# sensorboard.net
KiCad netlist of a schematic drawn in EAGLE
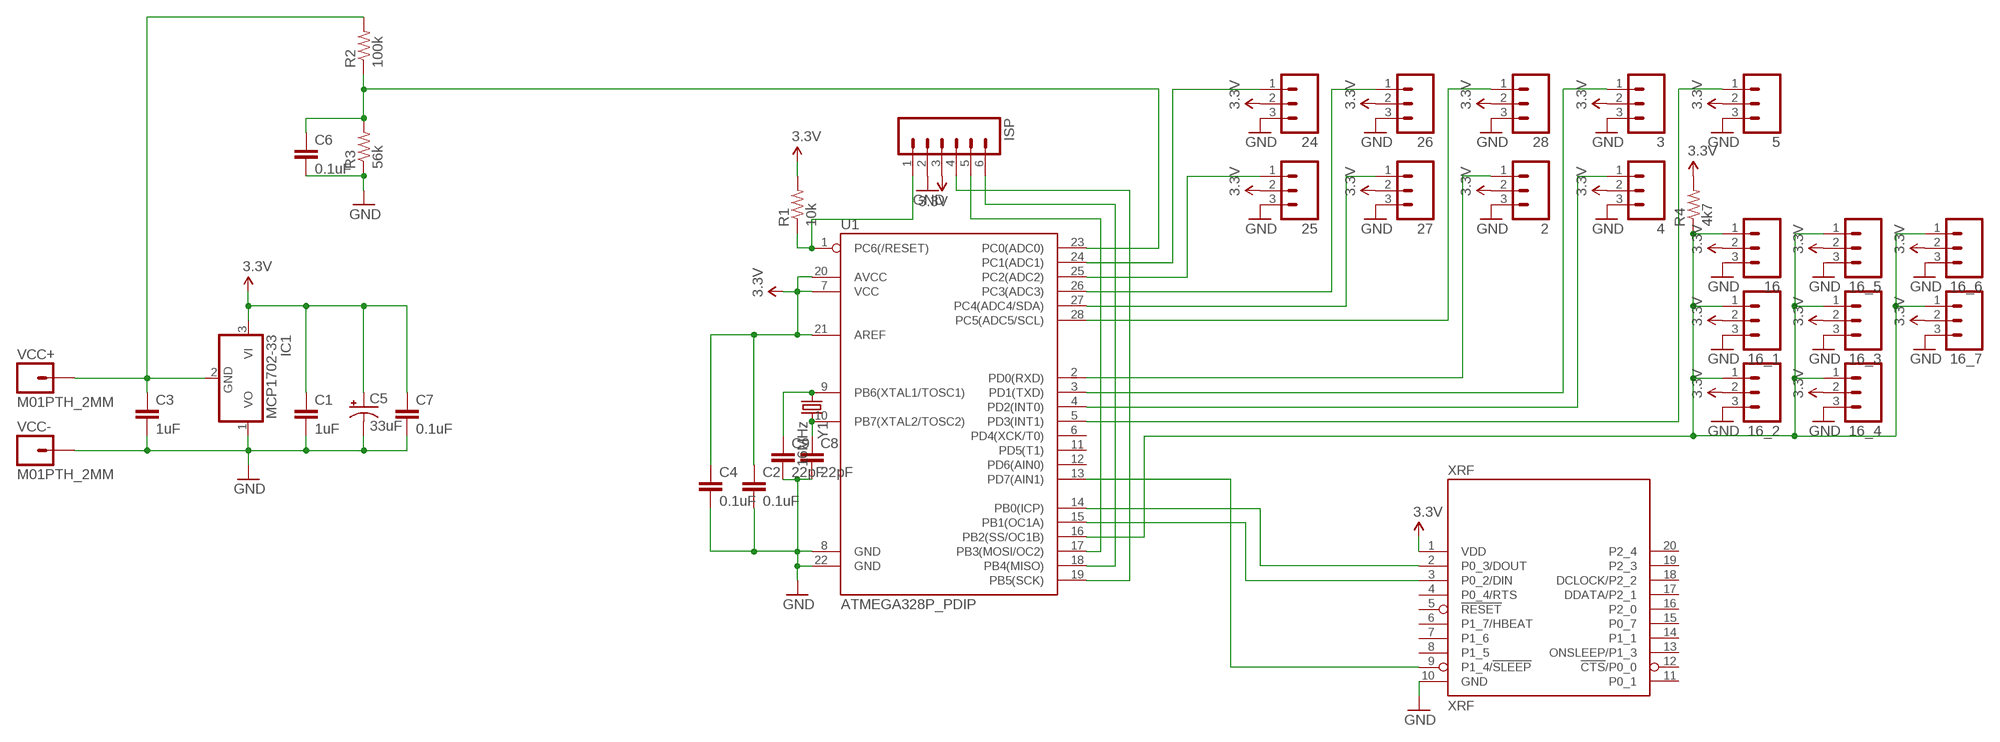
[diagram p0: schematic, sheet 1]

(export (version "E")
  (design (tool "Eeschema 10.0.6"))
  (components
    (comp (ref "2")
      (value "M031X03_NO_SILK")
      (footprint "eagle-import:1X03_NO_SILK")
      (libsource (lib "eagle-import") (part "M031X03_NO_SILK"))
    )
    (comp (ref "3")
      (value "M031X03_NO_SILK")
      (footprint "eagle-import:1X03_NO_SILK")
      (libsource (lib "eagle-import") (part "M031X03_NO_SILK"))
    )
    (comp (ref "4")
      (value "M031X03_NO_SILK")
      (footprint "eagle-import:1X03_NO_SILK")
      (libsource (lib "eagle-import") (part "M031X03_NO_SILK"))
    )
    (comp (ref "5")
      (value "M031X03_NO_SILK")
      (footprint "eagle-import:1X03_NO_SILK")
      (libsource (lib "eagle-import") (part "M031X03_NO_SILK"))
    )
    (comp (ref "16")
      (value "M031X03_NO_SILK")
      (footprint "eagle-import:1X03_NO_SILK")
      (libsource (lib "eagle-import") (part "M031X03_NO_SILK"))
    )
    (comp (ref "16_1")
      (value "M031X03_NO_SILK")
      (footprint "eagle-import:1X03_NO_SILK")
      (libsource (lib "eagle-import") (part "M031X03_NO_SILK"))
    )
    (comp (ref "16_2")
      (value "M031X03_NO_SILK")
      (footprint "eagle-import:1X03_NO_SILK")
      (libsource (lib "eagle-import") (part "M031X03_NO_SILK"))
    )
    (comp (ref "16_3")
      (value "M031X03_NO_SILK")
      (footprint "eagle-import:1X03_NO_SILK")
      (libsource (lib "eagle-import") (part "M031X03_NO_SILK"))
    )
    (comp (ref "16_4")
      (value "M031X03_NO_SILK")
      (footprint "eagle-import:1X03_NO_SILK")
      (libsource (lib "eagle-import") (part "M031X03_NO_SILK"))
    )
    (comp (ref "16_5")
      (value "M031X03_NO_SILK")
      (footprint "eagle-import:1X03_NO_SILK")
      (libsource (lib "eagle-import") (part "M031X03_NO_SILK"))
    )
    (comp (ref "16_6")
      (value "M031X03_NO_SILK")
      (footprint "eagle-import:1X03_NO_SILK")
      (libsource (lib "eagle-import") (part "M031X03_NO_SILK"))
    )
    (comp (ref "16_7")
      (value "M031X03_NO_SILK")
      (footprint "eagle-import:1X03_NO_SILK")
      (libsource (lib "eagle-import") (part "M031X03_NO_SILK"))
    )
    (comp (ref "24")
      (value "M031X03_NO_SILK")
      (footprint "eagle-import:1X03_NO_SILK")
      (libsource (lib "eagle-import") (part "M031X03_NO_SILK"))
    )
    (comp (ref "25")
      (value "M031X03_NO_SILK")
      (footprint "eagle-import:1X03_NO_SILK")
      (libsource (lib "eagle-import") (part "M031X03_NO_SILK"))
    )
    (comp (ref "26")
      (value "M031X03_NO_SILK")
      (footprint "eagle-import:1X03_NO_SILK")
      (libsource (lib "eagle-import") (part "M031X03_NO_SILK"))
    )
    (comp (ref "27")
      (value "M031X03_NO_SILK")
      (footprint "eagle-import:1X03_NO_SILK")
      (libsource (lib "eagle-import") (part "M031X03_NO_SILK"))
    )
    (comp (ref "28")
      (value "M031X03_NO_SILK")
      (footprint "eagle-import:1X03_NO_SILK")
      (libsource (lib "eagle-import") (part "M031X03_NO_SILK"))
    )
    (comp (ref "C1")
      (value "1uF")
      (footprint "eagle-import:CAP-PTH-SMALLEZ")
      (libsource (lib "eagle-import") (part "CAPEZ"))
    )
    (comp (ref "C2")
      (value "0.1uF")
      (footprint "eagle-import:CAP-PTH-SMALLEZ")
      (libsource (lib "eagle-import") (part "CAPEZ"))
    )
    (comp (ref "C3")
      (value "1uF")
      (footprint "eagle-import:CAP-PTH-SMALLEZ")
      (libsource (lib "eagle-import") (part "CAPEZ"))
    )
    (comp (ref "C4")
      (value "0.1uF")
      (footprint "eagle-import:CAP-PTH-SMALLEZ")
      (libsource (lib "eagle-import") (part "CAPEZ"))
    )
    (comp (ref "C5")
      (value "33uF")
      (footprint "eagle-import:CPOL-RADIAL-10UF-25V")
      (libsource (lib "eagle-import") (part "CAP_POLPTH2"))
    )
    (comp (ref "C6")
      (value "0.1uF")
      (footprint "eagle-import:CAP-PTH-SMALLEZ")
      (libsource (lib "eagle-import") (part "CAPEZ"))
    )
    (comp (ref "C7")
      (value "0.1uF")
      (footprint "eagle-import:CAP-PTH-SMALLEZ")
      (libsource (lib "eagle-import") (part "CAPEZ"))
    )
    (comp (ref "C8")
      (value "22pF")
      (footprint "eagle-import:CAP-PTH-SMALLEZ")
      (libsource (lib "eagle-import") (part "CAPEZ"))
    )
    (comp (ref "C9")
      (value "22pF")
      (footprint "eagle-import:CAP-PTH-SMALLEZ")
      (libsource (lib "eagle-import") (part "CAPEZ"))
    )
    (comp (ref "IC1")
      (value "MCP1702-33")
      (footprint "eagle-import:TO92")
      (libsource (lib "eagle-import") (part "78ZL05"))
    )
    (comp (ref "ISP")
      (value "M06SIP")
      (footprint "eagle-import:1X06")
      (libsource (lib "eagle-import") (part "M06SIP"))
    )
    (comp (ref "R1")
      (value "10k")
      (footprint "eagle-import:AXIAL-0.3EZ")
      (libsource (lib "eagle-import") (part "RESISTOREZ"))
    )
    (comp (ref "R2")
      (value "100k")
      (footprint "eagle-import:AXIAL-0.3EZ")
      (libsource (lib "eagle-import") (part "RESISTOREZ"))
    )
    (comp (ref "R3")
      (value "56k")
      (footprint "eagle-import:AXIAL-0.3EZ")
      (libsource (lib "eagle-import") (part "RESISTOREZ"))
    )
    (comp (ref "R4")
      (value "4k7")
      (footprint "eagle-import:AXIAL-0.3EZ")
      (libsource (lib "eagle-import") (part "RESISTOREZ"))
    )
    (comp (ref "U1")
      (value "ATMEGA328P_PDIP")
      (footprint "eagle-import:DIL28-3")
      (libsource (lib "eagle-import") (part "ATMEGA328P_PDIP"))
    )
    (comp (ref "VCC+")
      (value "M01PTH_2MM")
      (footprint "eagle-import:1X01_2MM")
      (libsource (lib "eagle-import") (part "M01PTH_2MM"))
    )
    (comp (ref "VCC-")
      (value "M01PTH_2MM")
      (footprint "eagle-import:1X01_2MM")
      (libsource (lib "eagle-import") (part "M01PTH_2MM"))
    )
    (comp (ref "XRF")
      (value "XRF")
      (footprint "eagle-import:XRF")
      (libsource (lib "eagle-import") (part "XRFXRF"))
    )
    (comp (ref "Y1")
      (value "16MHz")
      (footprint "eagle-import:HC49US")
      (libsource (lib "eagle-import") (part "CRYSTALHC49US"))
    )
  )
  (nets
    (net (code "1") (name "3.3V") (class "Default")
      (node (ref "16") (pin "2") (pinfunction "2_2") (pintype "passive"))
      (node (ref "16_1") (pin "2") (pinfunction "2_2") (pintype "passive"))
      (node (ref "16_2") (pin "2") (pinfunction "2_2") (pintype "passive"))
      (node (ref "16_3") (pin "2") (pinfunction "2_2") (pintype "passive"))
      (node (ref "16_4") (pin "2") (pinfunction "2_2") (pintype "passive"))
      (node (ref "16_5") (pin "2") (pinfunction "2_2") (pintype "passive"))
      (node (ref "16_6") (pin "2") (pinfunction "2_2") (pintype "passive"))
      (node (ref "16_7") (pin "2") (pinfunction "2_2") (pintype "passive"))
      (node (ref "2") (pin "2") (pinfunction "2_2") (pintype "passive"))
      (node (ref "24") (pin "2") (pinfunction "2_2") (pintype "passive"))
      (node (ref "25") (pin "2") (pinfunction "2_2") (pintype "passive"))
      (node (ref "26") (pin "2") (pinfunction "2_2") (pintype "passive"))
      (node (ref "27") (pin "2") (pinfunction "2_2") (pintype "passive"))
      (node (ref "28") (pin "2") (pinfunction "2_2") (pintype "passive"))
      (node (ref "3") (pin "2") (pinfunction "2_2") (pintype "passive"))
      (node (ref "4") (pin "2") (pinfunction "2_2") (pintype "passive"))
      (node (ref "5") (pin "2") (pinfunction "2_2") (pintype "passive"))
      (node (ref "C1") (pin "1") (pinfunction "1_1") (pintype "passive"))
      (node (ref "C2") (pin "1") (pinfunction "1_1") (pintype "passive"))
      (node (ref "C4") (pin "1") (pinfunction "1_1") (pintype "passive"))
      (node (ref "C5") (pin "1") (pinfunction "+_1") (pintype "passive"))
      (node (ref "C7") (pin "1") (pinfunction "1_1") (pintype "passive"))
      (node (ref "IC1") (pin "3") (pinfunction "VI_3") (pintype "input"))
      (node (ref "ISP") (pin "3") (pinfunction "3_3") (pintype "passive"))
      (node (ref "R1") (pin "P$2") (pinfunction "2_P$2") (pintype "passive"))
      (node (ref "R4") (pin "P$2") (pinfunction "2_P$2") (pintype "passive"))
      (node (ref "U1") (pin "20") (pinfunction "AVCC_20") (pintype "bidirectional"))
      (node (ref "U1") (pin "21") (pinfunction "AREF_21") (pintype "bidirectional"))
      (node (ref "U1") (pin "7") (pinfunction "VCC_7") (pintype "bidirectional"))
      (node (ref "XRF") (pin "1") (pinfunction "VDD_1") (pintype "power_in"))
    )
    (net (code "2") (name "GND") (class "Default")
      (node (ref "16") (pin "3") (pinfunction "3_3") (pintype "passive"))
      (node (ref "16_1") (pin "3") (pinfunction "3_3") (pintype "passive"))
      (node (ref "16_2") (pin "3") (pinfunction "3_3") (pintype "passive"))
      (node (ref "16_3") (pin "3") (pinfunction "3_3") (pintype "passive"))
      (node (ref "16_4") (pin "3") (pinfunction "3_3") (pintype "passive"))
      (node (ref "16_5") (pin "3") (pinfunction "3_3") (pintype "passive"))
      (node (ref "16_6") (pin "3") (pinfunction "3_3") (pintype "passive"))
      (node (ref "16_7") (pin "3") (pinfunction "3_3") (pintype "passive"))
      (node (ref "2") (pin "3") (pinfunction "3_3") (pintype "passive"))
      (node (ref "24") (pin "3") (pinfunction "3_3") (pintype "passive"))
      (node (ref "25") (pin "3") (pinfunction "3_3") (pintype "passive"))
      (node (ref "26") (pin "3") (pinfunction "3_3") (pintype "passive"))
      (node (ref "27") (pin "3") (pinfunction "3_3") (pintype "passive"))
      (node (ref "28") (pin "3") (pinfunction "3_3") (pintype "passive"))
      (node (ref "3") (pin "3") (pinfunction "3_3") (pintype "passive"))
      (node (ref "4") (pin "3") (pinfunction "3_3") (pintype "passive"))
      (node (ref "5") (pin "3") (pinfunction "3_3") (pintype "passive"))
      (node (ref "C1") (pin "2") (pinfunction "2_2") (pintype "passive"))
      (node (ref "C2") (pin "2") (pinfunction "2_2") (pintype "passive"))
      (node (ref "C3") (pin "2") (pinfunction "2_2") (pintype "passive"))
      (node (ref "C4") (pin "2") (pinfunction "2_2") (pintype "passive"))
      (node (ref "C5") (pin "2") (pinfunction "-_2") (pintype "passive"))
      (node (ref "C6") (pin "2") (pinfunction "2_2") (pintype "passive"))
      (node (ref "C7") (pin "2") (pinfunction "2_2") (pintype "passive"))
      (node (ref "C8") (pin "2") (pinfunction "2_2") (pintype "passive"))
      (node (ref "C9") (pin "2") (pinfunction "2_2") (pintype "passive"))
      (node (ref "IC1") (pin "1") (pinfunction "VO_1") (pintype "passive"))
      (node (ref "ISP") (pin "2") (pinfunction "2_2") (pintype "passive"))
      (node (ref "R3") (pin "P$1") (pinfunction "1_P$1") (pintype "passive"))
      (node (ref "U1") (pin "22") (pinfunction "GND_22") (pintype "bidirectional"))
      (node (ref "U1") (pin "8") (pinfunction "GND_8") (pintype "bidirectional"))
      (node (ref "VCC-") (pin "1") (pinfunction "1_1") (pintype "passive"))
      (node (ref "XRF") (pin "10") (pinfunction "GND_10") (pintype "power_in"))
    )
    (net (code "3") (name "Net-(IC1-GND)") (class "Default")
      (node (ref "C3") (pin "1") (pinfunction "1_1") (pintype "passive"))
      (node (ref "IC1") (pin "2") (pinfunction "GND_2") (pintype "passive"))
      (node (ref "R2") (pin "P$2") (pinfunction "2_P$2") (pintype "passive"))
      (node (ref "VCC+") (pin "1") (pinfunction "1_1") (pintype "passive"))
    )
    (net (code "4") (name "Net-(R1-1)") (class "Default")
      (node (ref "ISP") (pin "1") (pinfunction "1_1") (pintype "passive"))
      (node (ref "R1") (pin "P$1") (pinfunction "1_P$1") (pintype "passive"))
      (node (ref "U1") (pin "1") (pinfunction "PC6(/RESET)_1") (pintype "bidirectional"))
    )
    (net (code "5") (name "Net-(R2-1)") (class "Default")
      (node (ref "C6") (pin "1") (pinfunction "1_1") (pintype "passive"))
      (node (ref "R2") (pin "P$1") (pinfunction "1_P$1") (pintype "passive"))
      (node (ref "R3") (pin "P$2") (pinfunction "2_P$2") (pintype "passive"))
      (node (ref "U1") (pin "23") (pinfunction "PC0(ADC0)_23") (pintype "bidirectional"))
    )
    (net (code "6") (name "Net-(R4-1)") (class "Default")
      (node (ref "16") (pin "1") (pinfunction "1_1") (pintype "passive"))
      (node (ref "16_1") (pin "1") (pinfunction "1_1") (pintype "passive"))
      (node (ref "16_2") (pin "1") (pinfunction "1_1") (pintype "passive"))
      (node (ref "16_3") (pin "1") (pinfunction "1_1") (pintype "passive"))
      (node (ref "16_4") (pin "1") (pinfunction "1_1") (pintype "passive"))
      (node (ref "16_5") (pin "1") (pinfunction "1_1") (pintype "passive"))
      (node (ref "16_6") (pin "1") (pinfunction "1_1") (pintype "passive"))
      (node (ref "16_7") (pin "1") (pinfunction "1_1") (pintype "passive"))
      (node (ref "R4") (pin "P$1") (pinfunction "1_P$1") (pintype "passive"))
      (node (ref "U1") (pin "16") (pinfunction "PB2(SS/OC1B)_16") (pintype "bidirectional"))
    )
    (net (code "7") (name "Net-(U1-PB0(ICP))") (class "Default")
      (node (ref "U1") (pin "14") (pinfunction "PB0(ICP)_14") (pintype "bidirectional"))
      (node (ref "XRF") (pin "2") (pinfunction "P0_3/DOUT_2") (pintype "output"))
    )
    (net (code "8") (name "Net-(U1-PB1(OC1A))") (class "Default")
      (node (ref "U1") (pin "15") (pinfunction "PB1(OC1A)_15") (pintype "bidirectional"))
      (node (ref "XRF") (pin "3") (pinfunction "P0_2/DIN_3") (pintype "input"))
    )
    (net (code "9") (name "Net-(U1-PB3(MOSI{slash}OC2))") (class "Default")
      (node (ref "ISP") (pin "5") (pinfunction "5_5") (pintype "passive"))
      (node (ref "U1") (pin "17") (pinfunction "PB3(MOSI/OC2)_17") (pintype "bidirectional"))
    )
    (net (code "10") (name "Net-(U1-PB4(MISO))") (class "Default")
      (node (ref "ISP") (pin "6") (pinfunction "6_6") (pintype "passive"))
      (node (ref "U1") (pin "18") (pinfunction "PB4(MISO)_18") (pintype "bidirectional"))
    )
    (net (code "11") (name "Net-(U1-PB5(SCK))") (class "Default")
      (node (ref "ISP") (pin "4") (pinfunction "4_4") (pintype "passive"))
      (node (ref "U1") (pin "19") (pinfunction "PB5(SCK)_19") (pintype "bidirectional"))
    )
    (net (code "12") (name "Net-(U1-PB6(XTAL1{slash}TOSC1))") (class "Default")
      (node (ref "C9") (pin "1") (pinfunction "1_1") (pintype "passive"))
      (node (ref "U1") (pin "9") (pinfunction "PB6(XTAL1/TOSC1)_9") (pintype "bidirectional"))
      (node (ref "Y1") (pin "1") (pinfunction "1_1") (pintype "passive"))
    )
    (net (code "13") (name "Net-(U1-PB7(XTAL2{slash}TOSC2))") (class "Default")
      (node (ref "C8") (pin "1") (pinfunction "1_1") (pintype "passive"))
      (node (ref "U1") (pin "10") (pinfunction "PB7(XTAL2/TOSC2)_10") (pintype "bidirectional"))
      (node (ref "Y1") (pin "2") (pinfunction "2_2") (pintype "passive"))
    )
    (net (code "14") (name "Net-(U1-PC1(ADC1))") (class "Default")
      (node (ref "24") (pin "1") (pinfunction "1_1") (pintype "passive"))
      (node (ref "U1") (pin "24") (pinfunction "PC1(ADC1)_24") (pintype "bidirectional"))
    )
    (net (code "15") (name "Net-(U1-PC2(ADC2))") (class "Default")
      (node (ref "25") (pin "1") (pinfunction "1_1") (pintype "passive"))
      (node (ref "U1") (pin "25") (pinfunction "PC2(ADC2)_25") (pintype "bidirectional"))
    )
    (net (code "16") (name "Net-(U1-PC3(ADC3))") (class "Default")
      (node (ref "26") (pin "1") (pinfunction "1_1") (pintype "passive"))
      (node (ref "U1") (pin "26") (pinfunction "PC3(ADC3)_26") (pintype "bidirectional"))
    )
    (net (code "17") (name "Net-(U1-PC4(ADC4{slash}SDA))") (class "Default")
      (node (ref "27") (pin "1") (pinfunction "1_1") (pintype "passive"))
      (node (ref "U1") (pin "27") (pinfunction "PC4(ADC4/SDA)_27") (pintype "bidirectional"))
    )
    (net (code "18") (name "Net-(U1-PC5(ADC5{slash}SCL))") (class "Default")
      (node (ref "28") (pin "1") (pinfunction "1_1") (pintype "passive"))
      (node (ref "U1") (pin "28") (pinfunction "PC5(ADC5/SCL)_28") (pintype "bidirectional"))
    )
    (net (code "19") (name "Net-(U1-PD0(RXD))") (class "Default")
      (node (ref "2") (pin "1") (pinfunction "1_1") (pintype "passive"))
      (node (ref "U1") (pin "2") (pinfunction "PD0(RXD)_2") (pintype "bidirectional"))
    )
    (net (code "20") (name "Net-(U1-PD1(TXD))") (class "Default")
      (node (ref "3") (pin "1") (pinfunction "1_1") (pintype "passive"))
      (node (ref "U1") (pin "3") (pinfunction "PD1(TXD)_3") (pintype "bidirectional"))
    )
    (net (code "21") (name "Net-(U1-PD2(INT0))") (class "Default")
      (node (ref "4") (pin "1") (pinfunction "1_1") (pintype "passive"))
      (node (ref "U1") (pin "4") (pinfunction "PD2(INT0)_4") (pintype "bidirectional"))
    )
    (net (code "22") (name "Net-(U1-PD3(INT1))") (class "Default")
      (node (ref "5") (pin "1") (pinfunction "1_1") (pintype "passive"))
      (node (ref "U1") (pin "5") (pinfunction "PD3(INT1)_5") (pintype "bidirectional"))
    )
    (net (code "23") (name "Net-(U1-PD7(AIN1))") (class "Default")
      (node (ref "U1") (pin "13") (pinfunction "PD7(AIN1)_13") (pintype "bidirectional"))
      (node (ref "XRF") (pin "9") (pinfunction "P1_4/~{SLEEP}_9") (pintype "bidirectional"))
    )
    (net (code "24") (name "unconnected-(U1-PD4(XCK{slash}T0)-Pad6)") (class "Default")
      (node (ref "U1") (pin "6") (pinfunction "PD4(XCK/T0)_6") (pintype "bidirectional"))
    )
    (net (code "25") (name "unconnected-(U1-PD5(T1)-Pad11)") (class "Default")
      (node (ref "U1") (pin "11") (pinfunction "PD5(T1)_11") (pintype "bidirectional"))
    )
    (net (code "26") (name "unconnected-(U1-PD6(AIN0)-Pad12)") (class "Default")
      (node (ref "U1") (pin "12") (pinfunction "PD6(AIN0)_12") (pintype "bidirectional"))
    )
    (net (code "27") (name "unconnected-(XRF-DCLOCK{slash}P2_2-Pad18)") (class "Default")
      (node (ref "XRF") (pin "18") (pinfunction "DCLOCK/P2_2_18") (pintype "bidirectional"))
    )
    (net (code "28") (name "unconnected-(XRF-DDATA{slash}P2_1-Pad17)") (class "Default")
      (node (ref "XRF") (pin "17") (pinfunction "DDATA/P2_1_17") (pintype "bidirectional"))
    )
    (net (code "29") (name "unconnected-(XRF-ONSLEEP{slash}P1_3-Pad13)") (class "Default")
      (node (ref "XRF") (pin "13") (pinfunction "ONSLEEP/P1_3_13") (pintype "bidirectional"))
    )
    (net (code "30") (name "unconnected-(XRF-P0_1-Pad11)") (class "Default")
      (node (ref "XRF") (pin "11") (pinfunction "P0_1_11") (pintype "bidirectional"))
    )
    (net (code "31") (name "unconnected-(XRF-P0_4{slash}RTS-Pad4)") (class "Default")
      (node (ref "XRF") (pin "4") (pinfunction "P0_4/RTS_4") (pintype "bidirectional"))
    )
    (net (code "32") (name "unconnected-(XRF-P0_7-Pad15)") (class "Default")
      (node (ref "XRF") (pin "15") (pinfunction "P0_7_15") (pintype "bidirectional"))
    )
    (net (code "33") (name "unconnected-(XRF-P1_1-Pad14)") (class "Default")
      (node (ref "XRF") (pin "14") (pinfunction "P1_1_14") (pintype "bidirectional"))
    )
    (net (code "34") (name "unconnected-(XRF-P1_5-Pad8)") (class "Default")
      (node (ref "XRF") (pin "8") (pinfunction "P1_5_8") (pintype "bidirectional"))
    )
    (net (code "35") (name "unconnected-(XRF-P1_6-Pad7)") (class "Default")
      (node (ref "XRF") (pin "7") (pinfunction "P1_6_7") (pintype "bidirectional"))
    )
    (net (code "36") (name "unconnected-(XRF-P1_7{slash}HBEAT-Pad6)") (class "Default")
      (node (ref "XRF") (pin "6") (pinfunction "P1_7/HBEAT_6") (pintype "bidirectional"))
    )
    (net (code "37") (name "unconnected-(XRF-P2_0-Pad16)") (class "Default")
      (node (ref "XRF") (pin "16") (pinfunction "P2_0_16") (pintype "input"))
    )
    (net (code "38") (name "unconnected-(XRF-P2_3-Pad19)") (class "Default")
      (node (ref "XRF") (pin "19") (pinfunction "P2_3_19") (pintype "bidirectional"))
    )
    (net (code "39") (name "unconnected-(XRF-P2_4-Pad20)") (class "Default")
      (node (ref "XRF") (pin "20") (pinfunction "P2_4_20") (pintype "bidirectional"))
    )
    (net (code "40") (name "unconnected-(XRF-~{CTS}{slash}P0_0-Pad12)") (class "Default")
      (node (ref "XRF") (pin "12") (pinfunction "~{CTS}/P0_0_12") (pintype "output"))
    )
    (net (code "41") (name "unconnected-(XRF-~{RESET}-Pad5)") (class "Default")
      (node (ref "XRF") (pin "5") (pinfunction "~{RESET}_5") (pintype "input"))
    )
  )
)
